# DSD_SDR_MainBoard_Quad.net
KiCad netlist of a schematic drawn in Altium Designer
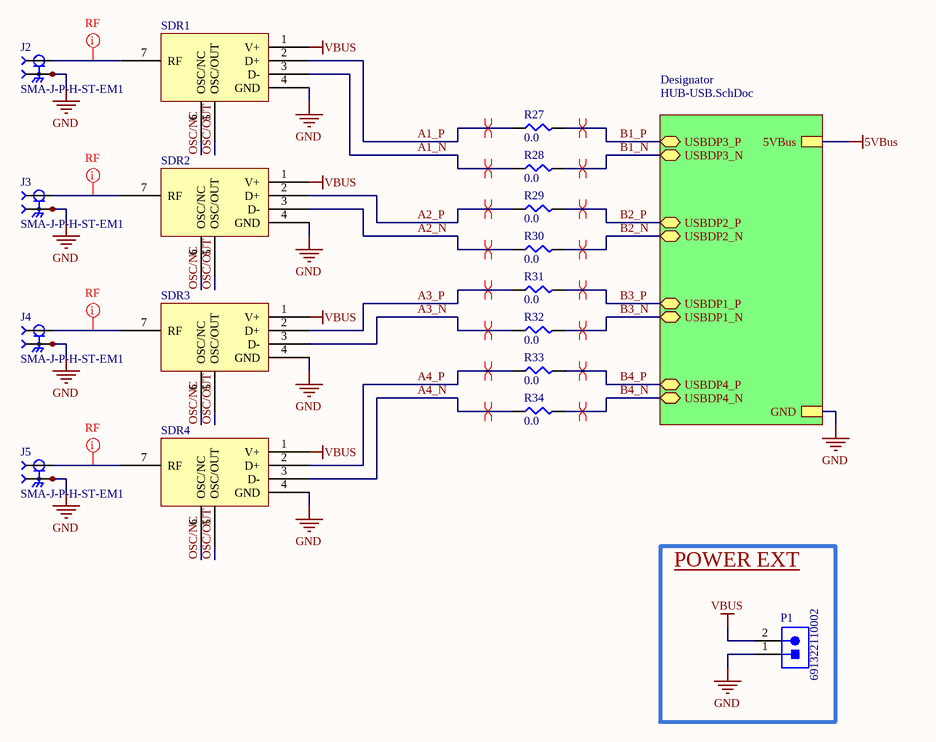
[diagram p0: DSD_SDR_MainBoard_Quad.SchDoc]

(export (version "E")
  (design (tool "Eeschema 10.0.6"))
  (components
    (comp (ref "J2")
      (value "SMA-J-P-H-ST-EM1")
      (footprint "SAMTEC_SMA-J-P-H-ST-EM1")
      (description "SMA Connector Jack, Female Socket 50Ohm Board Edge, End Launch Solder")
      (fields (field (name "MF") "Samtec"))
      (libsource (lib "SMA-J-P-H-ST-EM1") (part "SMA-J-P-H-ST-EM1"))
    )
    (comp (ref "J3")
      (value "SMA-J-P-H-ST-EM1")
      (footprint "SAMTEC_SMA-J-P-H-ST-EM1")
      (description "SMA Connector Jack, Female Socket 50Ohm Board Edge, End Launch Solder")
      (fields (field (name "MF") "Samtec"))
      (libsource (lib "SMA-J-P-H-ST-EM1") (part "SMA-J-P-H-ST-EM1"))
    )
    (comp (ref "J4")
      (value "SMA-J-P-H-ST-EM1")
      (footprint "SAMTEC_SMA-J-P-H-ST-EM1")
      (description "SMA Connector Jack, Female Socket 50Ohm Board Edge, End Launch Solder")
      (fields (field (name "MF") "Samtec"))
      (libsource (lib "SMA-J-P-H-ST-EM1") (part "SMA-J-P-H-ST-EM1"))
    )
    (comp (ref "J5")
      (value "SMA-J-P-H-ST-EM1")
      (footprint "SAMTEC_SMA-J-P-H-ST-EM1")
      (description "SMA Connector Jack, Female Socket 50Ohm Board Edge, End Launch Solder")
      (fields (field (name "MF") "Samtec"))
      (libsource (lib "SMA-J-P-H-ST-EM1") (part "SMA-J-P-H-ST-EM1"))
    )
    (comp (ref "P1")
      (value "691322110002")
      (footprint "691322110002")
      (description "WR-TBL Serie 3221 Horizontal PCB Header, Pluggable, THT, pitch 3.5mm, 2p")
      (fields (field (name "MANUFACTURER") "Wurth Elektronik"))
      (libsource (lib "Altium_WR-TBL (rev21a)") (part "691322110002"))
    )
    (comp (ref "R27")
      (value "0.0")
      (footprint "SMD-0603-RES")
      (description "RES SMD 0.0OHM JUMPER 1/10W 0603")
      (fields (field (name "PART NUMBER") "ERJ-3GEY0R00V") (field (name "DIGI-KEY PART NUMBER") "P0.0GCT-ND"))
      (libsource (lib "res_panasonic_erj_xls") (part "RESISTOR"))
    )
    (comp (ref "R28")
      (value "0.0")
      (footprint "SMD-0603-RES")
      (description "RES SMD 0.0OHM JUMPER 1/10W 0603")
      (fields (field (name "PART NUMBER") "ERJ-3GEY0R00V") (field (name "DIGI-KEY PART NUMBER") "P0.0GCT-ND"))
      (libsource (lib "res_panasonic_erj_xls") (part "RESISTOR"))
    )
    (comp (ref "R29")
      (value "0.0")
      (footprint "SMD-0603-RES")
      (description "RES SMD 0.0OHM JUMPER 1/10W 0603")
      (fields (field (name "PART NUMBER") "ERJ-3GEY0R00V") (field (name "DIGI-KEY PART NUMBER") "P0.0GCT-ND"))
      (libsource (lib "res_panasonic_erj_xls") (part "RESISTOR"))
    )
    (comp (ref "R30")
      (value "0.0")
      (footprint "SMD-0603-RES")
      (description "RES SMD 0.0OHM JUMPER 1/10W 0603")
      (fields (field (name "PART NUMBER") "ERJ-3GEY0R00V") (field (name "DIGI-KEY PART NUMBER") "P0.0GCT-ND"))
      (libsource (lib "res_panasonic_erj_xls") (part "RESISTOR"))
    )
    (comp (ref "R31")
      (value "0.0")
      (footprint "SMD-0603-RES")
      (description "RES SMD 0.0OHM JUMPER 1/10W 0603")
      (fields (field (name "PART NUMBER") "ERJ-3GEY0R00V") (field (name "DIGI-KEY PART NUMBER") "P0.0GCT-ND"))
      (libsource (lib "res_panasonic_erj_xls") (part "RESISTOR"))
    )
    (comp (ref "R32")
      (value "0.0")
      (footprint "SMD-0603-RES")
      (description "RES SMD 0.0OHM JUMPER 1/10W 0603")
      (fields (field (name "PART NUMBER") "ERJ-3GEY0R00V") (field (name "DIGI-KEY PART NUMBER") "P0.0GCT-ND"))
      (libsource (lib "res_panasonic_erj_xls") (part "RESISTOR"))
    )
    (comp (ref "R33")
      (value "0.0")
      (footprint "SMD-0603-RES")
      (description "RES SMD 0.0OHM JUMPER 1/10W 0603")
      (fields (field (name "PART NUMBER") "ERJ-3GEY0R00V") (field (name "DIGI-KEY PART NUMBER") "P0.0GCT-ND"))
      (libsource (lib "res_panasonic_erj_xls") (part "RESISTOR"))
    )
    (comp (ref "R34")
      (value "0.0")
      (footprint "SMD-0603-RES")
      (description "RES SMD 0.0OHM JUMPER 1/10W 0603")
      (fields (field (name "PART NUMBER") "ERJ-3GEY0R00V") (field (name "DIGI-KEY PART NUMBER") "P0.0GCT-ND"))
      (libsource (lib "res_panasonic_erj_xls") (part "RESISTOR"))
    )
    (comp (ref "SDR1")
      (value "SDR_Module")
      (footprint "SDR")
      (libsource (lib "SDR_Module") (part "SDR_Module"))
    )
    (comp (ref "SDR2")
      (value "SDR_Module")
      (footprint "SDR")
      (libsource (lib "SDR_Module") (part "SDR_Module"))
    )
    (comp (ref "SDR3")
      (value "SDR_Module")
      (footprint "SDR")
      (libsource (lib "SDR_Module") (part "SDR_Module"))
    )
    (comp (ref "SDR4")
      (value "SDR_Module")
      (footprint "SDR")
      (libsource (lib "SDR_Module") (part "SDR_Module"))
    )
  )
  (nets
    (net (code "1") (name "/A1_N") (class "Default")
      (node (ref "R28") (pin "1") (pinfunction "1_1") (pintype "passive"))
      (node (ref "SDR1") (pin "3") (pinfunction "D-_3") (pintype "passive"))
    )
    (net (code "2") (name "/A1_P") (class "Default")
      (node (ref "R27") (pin "1") (pinfunction "1_1") (pintype "passive"))
      (node (ref "SDR1") (pin "2") (pinfunction "D+_2") (pintype "passive"))
    )
    (net (code "3") (name "/A2_N") (class "Default")
      (node (ref "R30") (pin "1") (pinfunction "1_1") (pintype "passive"))
      (node (ref "SDR2") (pin "3") (pinfunction "D-_3") (pintype "passive"))
    )
    (net (code "4") (name "/A2_P") (class "Default")
      (node (ref "R29") (pin "1") (pinfunction "1_1") (pintype "passive"))
      (node (ref "SDR2") (pin "2") (pinfunction "D+_2") (pintype "passive"))
    )
    (net (code "5") (name "/A3_N") (class "Default")
      (node (ref "R32") (pin "1") (pinfunction "1_1") (pintype "passive"))
      (node (ref "SDR3") (pin "3") (pinfunction "D-_3") (pintype "passive"))
    )
    (net (code "6") (name "/A3_P") (class "Default")
      (node (ref "R31") (pin "1") (pinfunction "1_1") (pintype "passive"))
      (node (ref "SDR3") (pin "2") (pinfunction "D+_2") (pintype "passive"))
    )
    (net (code "7") (name "/A4_N") (class "Default")
      (node (ref "R34") (pin "1") (pinfunction "1_1") (pintype "passive"))
      (node (ref "SDR4") (pin "3") (pinfunction "D-_3") (pintype "passive"))
    )
    (net (code "8") (name "/A4_P") (class "Default")
      (node (ref "R33") (pin "1") (pinfunction "1_1") (pintype "passive"))
      (node (ref "SDR4") (pin "2") (pinfunction "D+_2") (pintype "passive"))
    )
    (net (code "9") (name "/B1_N") (class "Default")
      (node (ref "R28") (pin "2") (pinfunction "2_2") (pintype "passive"))
    )
    (net (code "10") (name "/B1_P") (class "Default")
      (node (ref "R27") (pin "2") (pinfunction "2_2") (pintype "passive"))
    )
    (net (code "11") (name "/B2_N") (class "Default")
      (node (ref "R30") (pin "2") (pinfunction "2_2") (pintype "passive"))
    )
    (net (code "12") (name "/B2_P") (class "Default")
      (node (ref "R29") (pin "2") (pinfunction "2_2") (pintype "passive"))
    )
    (net (code "13") (name "/B3_N") (class "Default")
      (node (ref "R32") (pin "2") (pinfunction "2_2") (pintype "passive"))
    )
    (net (code "14") (name "/B3_P") (class "Default")
      (node (ref "R31") (pin "2") (pinfunction "2_2") (pintype "passive"))
    )
    (net (code "15") (name "/B4_N") (class "Default")
      (node (ref "R34") (pin "2") (pinfunction "2_2") (pintype "passive"))
    )
    (net (code "16") (name "/B4_P") (class "Default")
      (node (ref "R33") (pin "2") (pinfunction "2_2") (pintype "passive"))
    )
    (net (code "17") (name "/OSC{slash}NC") (class "Default")
      (node (ref "SDR1") (pin "6") (pinfunction "OSC/NC_6") (pintype "passive"))
      (node (ref "SDR2") (pin "6") (pinfunction "OSC/NC_6") (pintype "passive"))
      (node (ref "SDR3") (pin "6") (pinfunction "OSC/NC_6") (pintype "passive"))
      (node (ref "SDR4") (pin "6") (pinfunction "OSC/NC_6") (pintype "passive"))
    )
    (net (code "18") (name "/OSC{slash}OUT") (class "Default")
      (node (ref "SDR1") (pin "5") (pinfunction "OSC/OUT_5") (pintype "passive"))
      (node (ref "SDR2") (pin "5") (pinfunction "OSC/OUT_5") (pintype "passive"))
      (node (ref "SDR3") (pin "5") (pinfunction "OSC/OUT_5") (pintype "passive"))
      (node (ref "SDR4") (pin "5") (pinfunction "OSC/OUT_5") (pintype "passive"))
    )
    (net (code "20") (name "GND") (class "Default")
      (node (ref "J2") (pin "2_1") (pinfunction "2_2_1") (pintype "passive"))
      (node (ref "J2") (pin "2_2") (pinfunction "2_2_2") (pintype "passive"))
      (node (ref "J2") (pin "3_1") (pinfunction "2_3_1") (pintype "passive"))
      (node (ref "J2") (pin "3_2") (pinfunction "2_3_2") (pintype "passive"))
      (node (ref "J3") (pin "2_1") (pinfunction "2_2_1") (pintype "passive"))
      (node (ref "J3") (pin "2_2") (pinfunction "2_2_2") (pintype "passive"))
      (node (ref "J3") (pin "3_1") (pinfunction "2_3_1") (pintype "passive"))
      (node (ref "J3") (pin "3_2") (pinfunction "2_3_2") (pintype "passive"))
      (node (ref "J4") (pin "2_1") (pinfunction "2_2_1") (pintype "passive"))
      (node (ref "J4") (pin "2_2") (pinfunction "2_2_2") (pintype "passive"))
      (node (ref "J4") (pin "3_1") (pinfunction "2_3_1") (pintype "passive"))
      (node (ref "J4") (pin "3_2") (pinfunction "2_3_2") (pintype "passive"))
      (node (ref "J5") (pin "2_1") (pinfunction "2_2_1") (pintype "passive"))
      (node (ref "J5") (pin "2_2") (pinfunction "2_2_2") (pintype "passive"))
      (node (ref "J5") (pin "3_1") (pinfunction "2_3_1") (pintype "passive"))
      (node (ref "J5") (pin "3_2") (pinfunction "2_3_2") (pintype "passive"))
      (node (ref "P1") (pin "1") (pinfunction "1_1") (pintype "passive"))
      (node (ref "SDR1") (pin "4") (pinfunction "GND_4") (pintype "passive"))
      (node (ref "SDR2") (pin "4") (pinfunction "GND_4") (pintype "passive"))
      (node (ref "SDR3") (pin "4") (pinfunction "GND_4") (pintype "passive"))
      (node (ref "SDR4") (pin "4") (pinfunction "GND_4") (pintype "passive"))
    )
    (net (code "21") (name "Net-(SDR1-RF)") (class "Default")
      (node (ref "J2") (pin "1") (pinfunction "1_1") (pintype "passive"))
      (node (ref "SDR1") (pin "7") (pinfunction "RF_7") (pintype "passive"))
    )
    (net (code "22") (name "Net-(SDR2-RF)") (class "Default")
      (node (ref "J3") (pin "1") (pinfunction "1_1") (pintype "passive"))
      (node (ref "SDR2") (pin "7") (pinfunction "RF_7") (pintype "passive"))
    )
    (net (code "23") (name "Net-(SDR3-RF)") (class "Default")
      (node (ref "J4") (pin "1") (pinfunction "1_1") (pintype "passive"))
      (node (ref "SDR3") (pin "7") (pinfunction "RF_7") (pintype "passive"))
    )
    (net (code "24") (name "Net-(SDR4-RF)") (class "Default")
      (node (ref "J5") (pin "1") (pinfunction "1_1") (pintype "passive"))
      (node (ref "SDR4") (pin "7") (pinfunction "RF_7") (pintype "passive"))
    )
    (net (code "25") (name "VBUS") (class "Default")
      (node (ref "P1") (pin "2") (pinfunction "2_2") (pintype "passive"))
      (node (ref "SDR1") (pin "1") (pinfunction "V+_1") (pintype "passive"))
      (node (ref "SDR2") (pin "1") (pinfunction "V+_1") (pintype "passive"))
      (node (ref "SDR3") (pin "1") (pinfunction "V+_1") (pintype "passive"))
      (node (ref "SDR4") (pin "1") (pinfunction "V+_1") (pintype "passive"))
    )
  )
)
